# RTC.net
KiCad netlist of a schematic drawn in Altium Designer
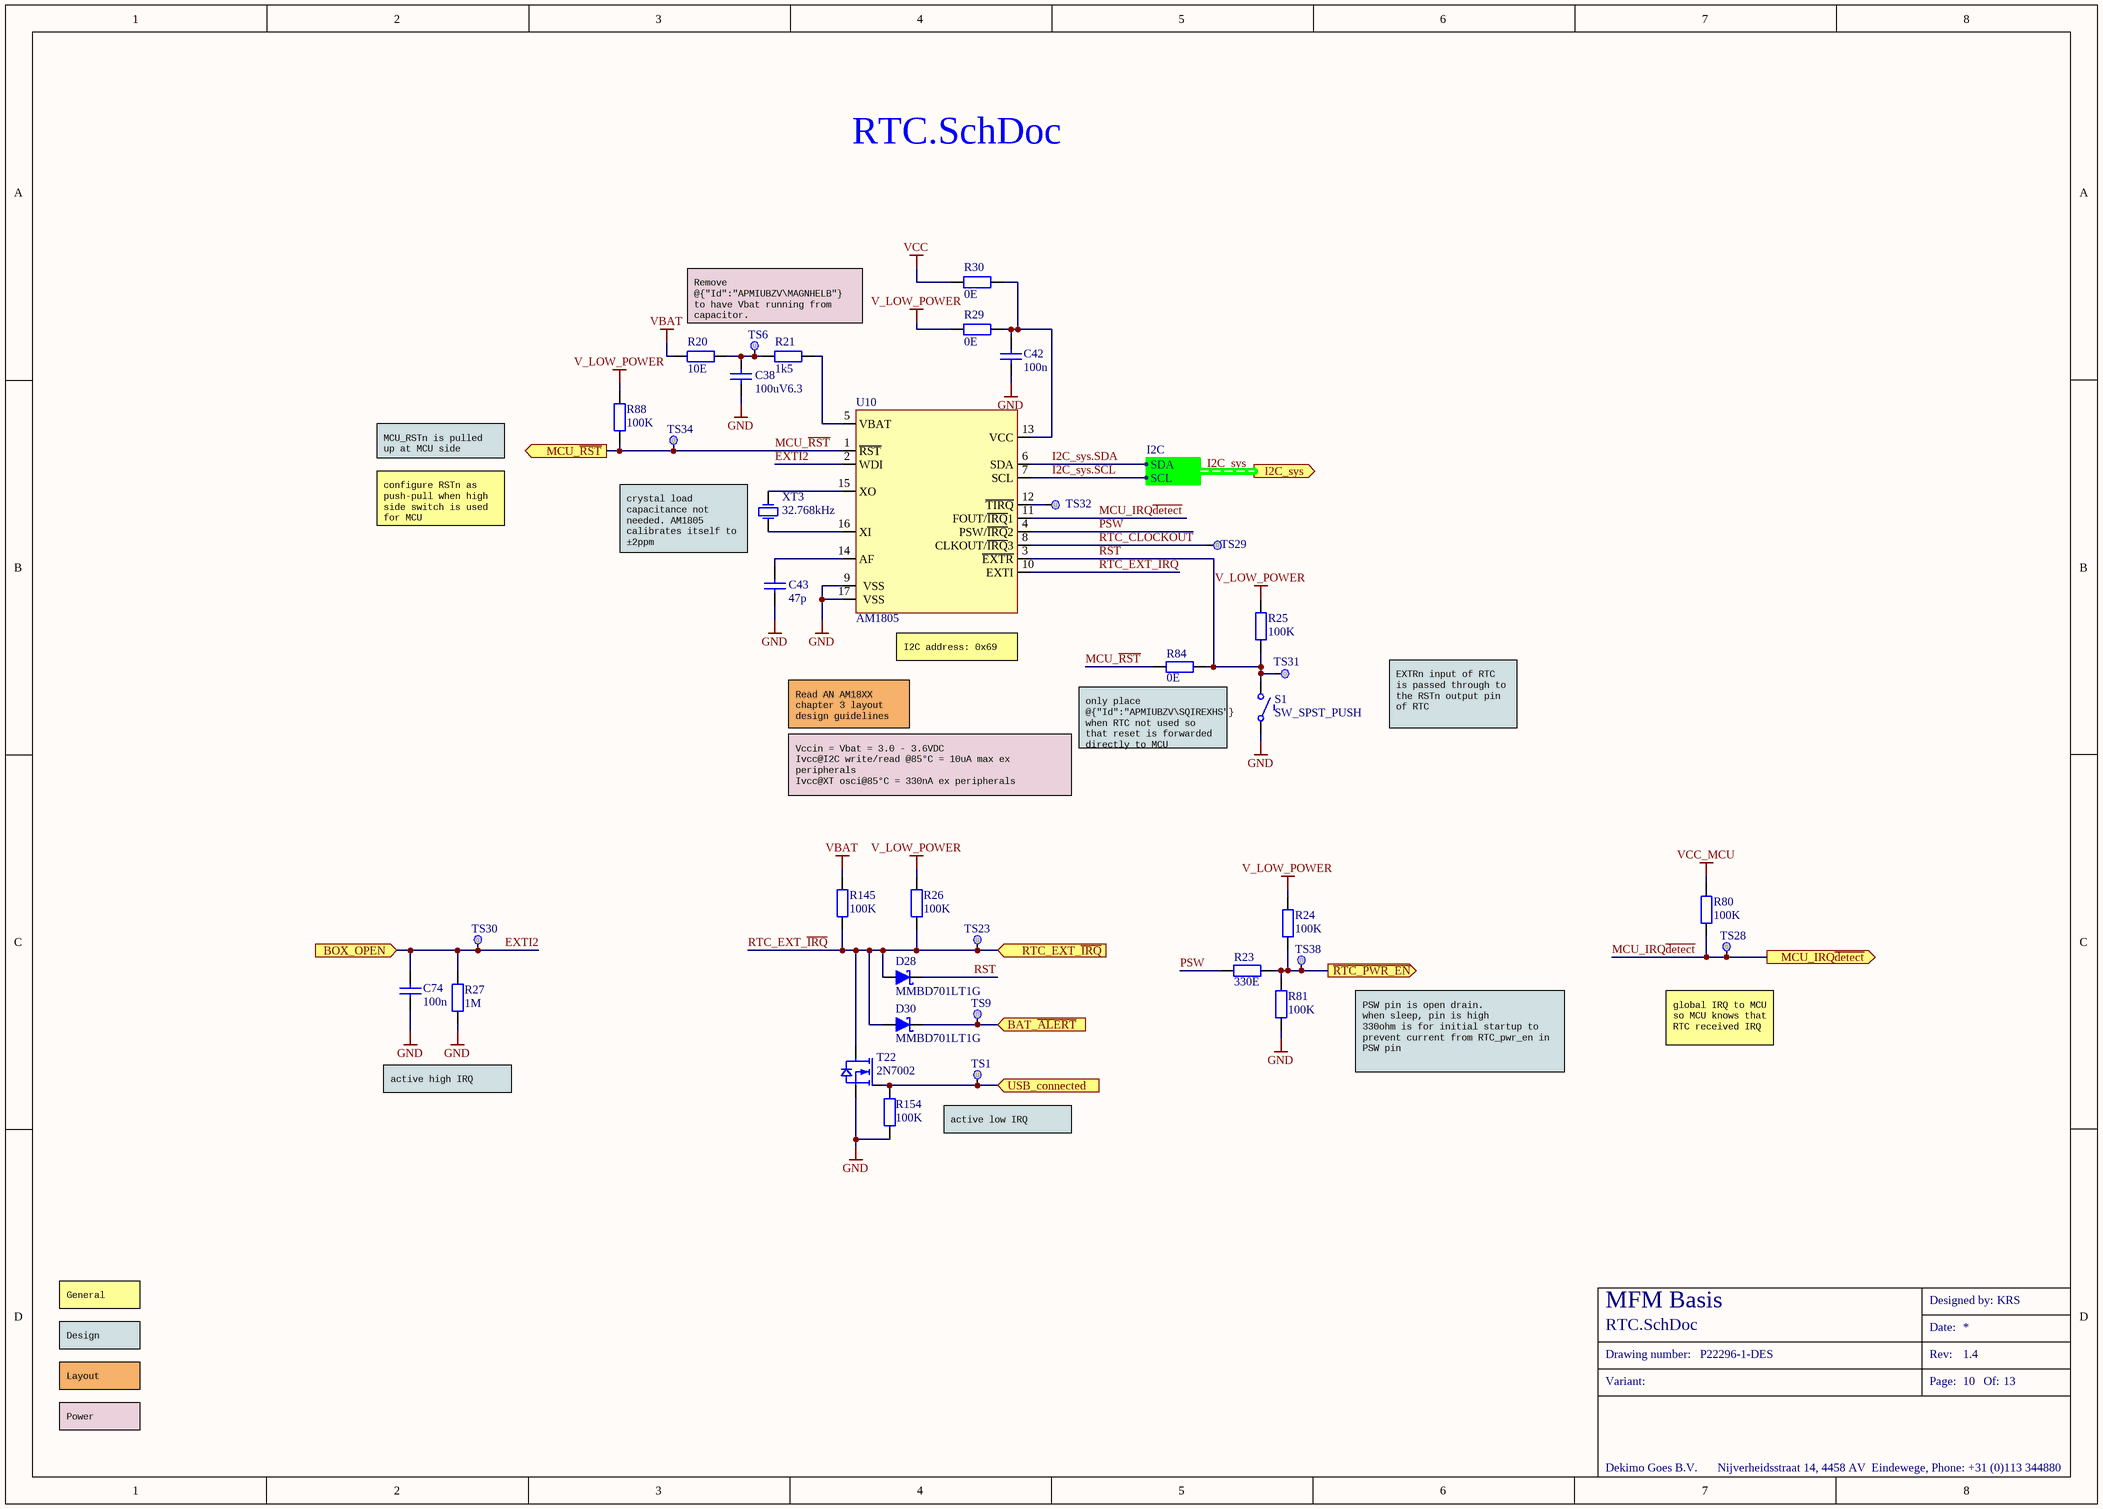
[diagram p0: RTC.SchDoc]

(export (version "E")
  (design (tool "Eeschema 10.0.6"))
  (components
    (comp (ref "C38")
      (value "100uV6.3")
      (footprint "CAPC3216X13N")
      (description "100uF 20% 6.3VX5R")
      (libsource (lib "") (part "Capacitor_NP_1"))
    )
    (comp (ref "C42")
      (value "100n")
      (footprint "CAPC1608X09N")
      (description "100nF 50V 10% X7R")
      (libsource (lib "DCI") (part "Capacitor_NP"))
    )
    (comp (ref "C43")
      (value "47p")
      (footprint "CAPC1608X09N")
      (description "47p 50V 5% NP0")
      (libsource (lib "") (part "Capacitor_NP_1"))
    )
    (comp (ref "C74")
      (value "100n")
      (footprint "CAPC1608X09N")
      (description "100nF 50V 10% X7R")
      (libsource (lib "DCI") (part "Capacitor_NP"))
    )
    (comp (ref "D28")
      (value "MMBD701LT1G")
      (footprint "SOT95P245X110-3N")
      (description "70V Low leakage 200nA")
      (libsource (lib "DCI") (part "D_Schottky"))
    )
    (comp (ref "D30")
      (value "MMBD701LT1G")
      (footprint "SOT95P245X110-3N")
      (description "70V Low leakage 200nA")
      (libsource (lib "DCI") (part "D_Schottky"))
    )
    (comp (ref "R20")
      (value "10E")
      (footprint "RESC1608X13N")
      (description "10E 0.1W 1%")
      (libsource (lib "DCI") (part "Resistor"))
    )
    (comp (ref "R21")
      (value "1k5")
      (footprint "RESC1608X13N")
      (description "1K5, 100mW, 1%")
      (libsource (lib "DCI") (part "Resistor"))
    )
    (comp (ref "R23")
      (value "330E")
      (footprint "RESC1608X13N")
      (description "330E, 100mW, 1%")
      (libsource (lib "DCI") (part "Resistor"))
    )
    (comp (ref "R24")
      (value "100K")
      (footprint "RESC1608X13N")
      (description "100k 100mW, 1%")
      (libsource (lib "") (part "Resistor_1"))
    )
    (comp (ref "R25")
      (value "100K")
      (footprint "RESC1608X13N")
      (description "100k 100mW, 1%")
      (libsource (lib "") (part "Resistor_1"))
    )
    (comp (ref "R26")
      (value "100K")
      (footprint "RESC1608X13N")
      (description "100k 100mW, 1%")
      (libsource (lib "") (part "Resistor_1"))
    )
    (comp (ref "R27")
      (value "1M")
      (footprint "RESC1608X13N")
      (description "1M 0.1W 1%")
      (libsource (lib "") (part "Resistor_1"))
    )
    (comp (ref "R29")
      (value "0E")
      (footprint "RESC1005X04N")
      (description "0E, 62.5mW, 1%")
      (libsource (lib "DCI") (part "Resistor"))
    )
    (comp (ref "R30")
      (value "0E")
      (footprint "RESC1005X04N")
      (description "0E, 62.5mW, 1%")
      (libsource (lib "DCI") (part "Resistor"))
    )
    (comp (ref "R80")
      (value "100K")
      (footprint "RESC1608X13N")
      (description "100k 100mW, 1%")
      (libsource (lib "") (part "Resistor_1"))
    )
    (comp (ref "R81")
      (value "100K")
      (footprint "RESC1608X13N")
      (description "100k 100mW, 1%")
      (libsource (lib "") (part "Resistor_1"))
    )
    (comp (ref "R84")
      (value "0E")
      (footprint "RESC1608X13N")
      (description "0E 100mW, 1%")
      (libsource (lib "DCI") (part "Resistor"))
    )
    (comp (ref "R88")
      (value "100K")
      (footprint "RESC1608X13N")
      (description "100k 100mW, 1%")
      (libsource (lib "") (part "Resistor_1"))
    )
    (comp (ref "R145")
      (value "100K")
      (footprint "RESC1608X13N")
      (description "100k 100mW, 1%")
      (libsource (lib "") (part "Resistor_1"))
    )
    (comp (ref "R154")
      (value "100K")
      (footprint "RESC1608X13N")
      (description "100k 100mW, 1%")
      (libsource (lib "") (part "Resistor_2"))
    )
    (comp (ref "S1")
      (value "SW_SPST_PUSH")
      (footprint "B3S-1000P")
      (description "PCB SPNO 6x6.6mm, h=4,3mm refl")
      (libsource (lib "DCI") (part "SW_SPST_PUSH"))
    )
    (comp (ref "T22")
      (value "2N7002")
      (footprint "SOT95P245X110_GSD-3N")
      (description "60V 115mA")
      (libsource (lib "DCI") (part "N_Mosfet"))
    )
    (comp (ref "TS1")
      (value "TESTPAD")
      (footprint "TESTPAD 2MM")
      (description "0.5mm Testpad SMD")
      (libsource (lib "PCBComponenten") (part "TESTPAD"))
    )
    (comp (ref "TS6")
      (value "TESTPAD")
      (footprint "TESTPAD 2MM")
      (description "0.5mm Testpad SMD")
      (libsource (lib "PCBComponenten") (part "TESTPAD"))
    )
    (comp (ref "TS9")
      (value "TESTPAD")
      (footprint "TESTPAD 2MM")
      (description "0.5mm Testpad SMD")
      (libsource (lib "PCBComponenten") (part "TESTPAD"))
    )
    (comp (ref "TS23")
      (value "TESTPAD")
      (footprint "TESTPAD 2MM")
      (description "0.5mm Testpad SMD")
      (libsource (lib "PCBComponenten") (part "TESTPAD"))
    )
    (comp (ref "TS28")
      (value "TESTPAD")
      (footprint "TESTPAD 2MM")
      (description "0.5mm Testpad SMD")
      (libsource (lib "PCBComponenten") (part "TESTPAD"))
    )
    (comp (ref "TS29")
      (value "TESTPAD")
      (footprint "TESTPAD 2MM")
      (description "0.5mm Testpad SMD")
      (libsource (lib "PCBComponenten") (part "TESTPAD"))
    )
    (comp (ref "TS30")
      (value "TESTPAD")
      (footprint "TESTPAD 2MM")
      (description "0.5mm Testpad SMD")
      (libsource (lib "PCBComponenten") (part "TESTPAD"))
    )
    (comp (ref "TS31")
      (value "TESTPAD")
      (footprint "TESTPAD 2MM")
      (description "0.5mm Testpad SMD")
      (libsource (lib "PCBComponenten") (part "TESTPAD"))
    )
    (comp (ref "TS32")
      (value "TESTPAD")
      (footprint "TESTPAD 2MM")
      (description "0.5mm Testpad SMD")
      (libsource (lib "PCBComponenten") (part "TESTPAD"))
    )
    (comp (ref "TS34")
      (value "TESTPAD")
      (footprint "TESTPAD 2MM")
      (description "0.5mm Testpad SMD")
      (libsource (lib "PCBComponenten") (part "TESTPAD"))
    )
    (comp (ref "TS38")
      (value "TESTPAD")
      (footprint "TESTPAD 2MM")
      (description "0.5mm Testpad SMD")
      (libsource (lib "PCBComponenten") (part "TESTPAD"))
    )
    (comp (ref "U10")
      (value "AM1805")
      (footprint "QFN-500G000-016")
      (description "Low power I2C RTC")
      (libsource (lib "DCI") (part "RTC_AM1805"))
    )
    (comp (ref "XT3")
      (value "32.768kHz")
      (footprint "CHIP2PINSM127P600-8N")
      (description "32.768kHz 20ppm 12.5pF")
      (libsource (lib "DCI") (part "XTAL"))
    )
  )
  (nets
    (net (code "2") (name "/BAT_~{ALERT}") (class "Default")
      (node (ref "D30") (pin "C") (pinfunction "C_C") (pintype "passive"))
      (node (ref "TS9") (pin "1") (pinfunction "TP_1") (pintype "passive"))
    )
    (net (code "3") (name "/EXTI2") (class "Default")
      (node (ref "C74") (pin "2") (pinfunction "2_2") (pintype "passive"))
      (node (ref "R27") (pin "2") (pinfunction "2_2") (pintype "passive"))
      (node (ref "TS30") (pin "1") (pinfunction "TP_1") (pintype "passive"))
      (node (ref "U10") (pin "2") (pinfunction "WDI_2") (pintype "passive"))
    )
    (net (code "4") (name "/I2C_sys.SCL") (class "Default")
      (node (ref "U10") (pin "7") (pinfunction "SCL_7") (pintype "passive"))
    )
    (net (code "5") (name "/I2C_sys.SDA") (class "Default")
      (node (ref "U10") (pin "6") (pinfunction "SDA_6") (pintype "passive"))
    )
    (net (code "7") (name "/MCU_IRQ~{detect}") (class "Default")
      (node (ref "R80") (pin "1") (pinfunction "1_1") (pintype "passive"))
      (node (ref "TS28") (pin "1") (pinfunction "TP_1") (pintype "passive"))
      (node (ref "U10") (pin "11") (pinfunction "FOUT/~{IRQ}1_11") (pintype "passive"))
    )
    (net (code "8") (name "/MCU_~{RST}") (class "Default")
      (node (ref "R84") (pin "1") (pinfunction "1_1") (pintype "passive"))
      (node (ref "R88") (pin "1") (pinfunction "1_1") (pintype "passive"))
      (node (ref "TS34") (pin "1") (pinfunction "TP_1") (pintype "passive"))
      (node (ref "U10") (pin "1") (pinfunction "~{RST}_1") (pintype "passive"))
    )
    (net (code "9") (name "/PSW") (class "Default")
      (node (ref "R23") (pin "1") (pinfunction "1_1") (pintype "passive"))
      (node (ref "U10") (pin "4") (pinfunction "PSW/~{IRQ}2_4") (pintype "passive"))
    )
    (net (code "10") (name "/RST") (class "Default")
      (node (ref "D28") (pin "C") (pinfunction "C_C") (pintype "passive"))
      (node (ref "R25") (pin "1") (pinfunction "1_1") (pintype "passive"))
      (node (ref "R84") (pin "2") (pinfunction "2_2") (pintype "passive"))
      (node (ref "S1") (pin "NO1") (pinfunction "NO_NO1") (pintype "passive"))
      (node (ref "TS31") (pin "1") (pinfunction "TP_1") (pintype "passive"))
      (node (ref "U10") (pin "3") (pinfunction "~{EXTR}_3") (pintype "passive"))
    )
    (net (code "11") (name "/RTC_CLOCKOUT") (class "Default")
      (node (ref "TS29") (pin "1") (pinfunction "TP_1") (pintype "passive"))
      (node (ref "U10") (pin "8") (pinfunction "CLKOUT/~{IRQ}3_8") (pintype "passive"))
    )
    (net (code "12") (name "/RTC_EXT_~{IRQ}") (class "Default")
      (node (ref "D28") (pin "A") (pinfunction "A_A") (pintype "passive"))
      (node (ref "D30") (pin "A") (pinfunction "A_A") (pintype "passive"))
      (node (ref "R145") (pin "1") (pinfunction "1_1") (pintype "passive"))
      (node (ref "R26") (pin "1") (pinfunction "1_1") (pintype "passive"))
      (node (ref "T22") (pin "D") (pinfunction "D_D") (pintype "passive"))
      (node (ref "TS23") (pin "1") (pinfunction "TP_1") (pintype "passive"))
      (node (ref "U10") (pin "10") (pinfunction "EXTI_10") (pintype "passive"))
    )
    (net (code "13") (name "/USB_connected") (class "Default")
      (node (ref "R154") (pin "2") (pinfunction "2_2") (pintype "passive"))
      (node (ref "T22") (pin "G") (pinfunction "G_G") (pintype "passive"))
      (node (ref "TS1") (pin "1") (pinfunction "TP_1") (pintype "passive"))
    )
    (net (code "14") (name "/~{RTC_PWR_EN}") (class "Default")
      (node (ref "R23") (pin "2") (pinfunction "2_2") (pintype "passive"))
      (node (ref "R24") (pin "1") (pinfunction "1_1") (pintype "passive"))
      (node (ref "R81") (pin "2") (pinfunction "2_2") (pintype "passive"))
      (node (ref "TS38") (pin "1") (pinfunction "TP_1") (pintype "passive"))
    )
    (net (code "15") (name "GND") (class "Default")
      (node (ref "C38") (pin "1") (pinfunction "1_1") (pintype "passive"))
      (node (ref "C42") (pin "1") (pinfunction "1_1") (pintype "passive"))
      (node (ref "C43") (pin "1") (pinfunction "1_1") (pintype "passive"))
      (node (ref "C74") (pin "1") (pinfunction "1_1") (pintype "passive"))
      (node (ref "R154") (pin "1") (pinfunction "1_1") (pintype "passive"))
      (node (ref "R27") (pin "1") (pinfunction "1_1") (pintype "passive"))
      (node (ref "R81") (pin "1") (pinfunction "1_1") (pintype "passive"))
      (node (ref "S1") (pin "COM1") (pinfunction "COMMON_COM1") (pintype "passive"))
      (node (ref "T22") (pin "S") (pinfunction "S_S") (pintype "passive"))
      (node (ref "U10") (pin "17") (pinfunction "VSS_17") (pintype "passive"))
      (node (ref "U10") (pin "9") (pinfunction "VSS_9") (pintype "passive"))
    )
    (net (code "16") (name "Net-(TS6-TP)") (class "Default")
      (node (ref "C38") (pin "2") (pinfunction "2_2") (pintype "passive"))
      (node (ref "R20") (pin "2") (pinfunction "2_2") (pintype "passive"))
      (node (ref "R21") (pin "1") (pinfunction "1_1") (pintype "passive"))
      (node (ref "TS6") (pin "1") (pinfunction "TP_1") (pintype "passive"))
    )
    (net (code "17") (name "Net-(TS32-TP)") (class "Default")
      (node (ref "TS32") (pin "1") (pinfunction "TP_1") (pintype "passive"))
      (node (ref "U10") (pin "12") (pinfunction "~{TIRQ}_12") (pintype "passive"))
    )
    (net (code "18") (name "Net-(U10-AF)") (class "Default")
      (node (ref "C43") (pin "2") (pinfunction "2_2") (pintype "passive"))
      (node (ref "U10") (pin "14") (pinfunction "AF_14") (pintype "passive"))
    )
    (net (code "19") (name "Net-(U10-VBAT)") (class "Default")
      (node (ref "R21") (pin "2") (pinfunction "2_2") (pintype "passive"))
      (node (ref "U10") (pin "5") (pinfunction "VBAT_5") (pintype "passive"))
    )
    (net (code "20") (name "Net-(U10-VCC)") (class "Default")
      (node (ref "C42") (pin "2") (pinfunction "2_2") (pintype "passive"))
      (node (ref "R29") (pin "2") (pinfunction "2_2") (pintype "passive"))
      (node (ref "R30") (pin "2") (pinfunction "2_2") (pintype "passive"))
      (node (ref "U10") (pin "13") (pinfunction "VCC_13") (pintype "passive"))
    )
    (net (code "21") (name "Net-(U10-XI)") (class "Default")
      (node (ref "U10") (pin "16") (pinfunction "XI_16") (pintype "passive"))
      (node (ref "XT3") (pin "1") (pinfunction "OSC1_1") (pintype "passive"))
    )
    (net (code "22") (name "Net-(U10-XO)") (class "Default")
      (node (ref "U10") (pin "15") (pinfunction "XO_15") (pintype "passive"))
      (node (ref "XT3") (pin "2") (pinfunction "OSC2_2") (pintype "passive"))
    )
    (net (code "23") (name "VBAT") (class "Default")
      (node (ref "R145") (pin "2") (pinfunction "2_2") (pintype "passive"))
      (node (ref "R20") (pin "1") (pinfunction "1_1") (pintype "passive"))
    )
    (net (code "24") (name "VCC") (class "Default")
      (node (ref "R30") (pin "1") (pinfunction "1_1") (pintype "passive"))
    )
    (net (code "25") (name "VCC_MCU") (class "Default")
      (node (ref "R80") (pin "2") (pinfunction "2_2") (pintype "passive"))
    )
    (net (code "26") (name "V_LOW_POWER") (class "Default")
      (node (ref "R24") (pin "2") (pinfunction "2_2") (pintype "passive"))
      (node (ref "R25") (pin "2") (pinfunction "2_2") (pintype "passive"))
      (node (ref "R26") (pin "2") (pinfunction "2_2") (pintype "passive"))
      (node (ref "R29") (pin "1") (pinfunction "1_1") (pintype "passive"))
      (node (ref "R88") (pin "2") (pinfunction "2_2") (pintype "passive"))
    )
  )
)
